# sixties2.net
KiCad netlist of a schematic drawn in EAGLE
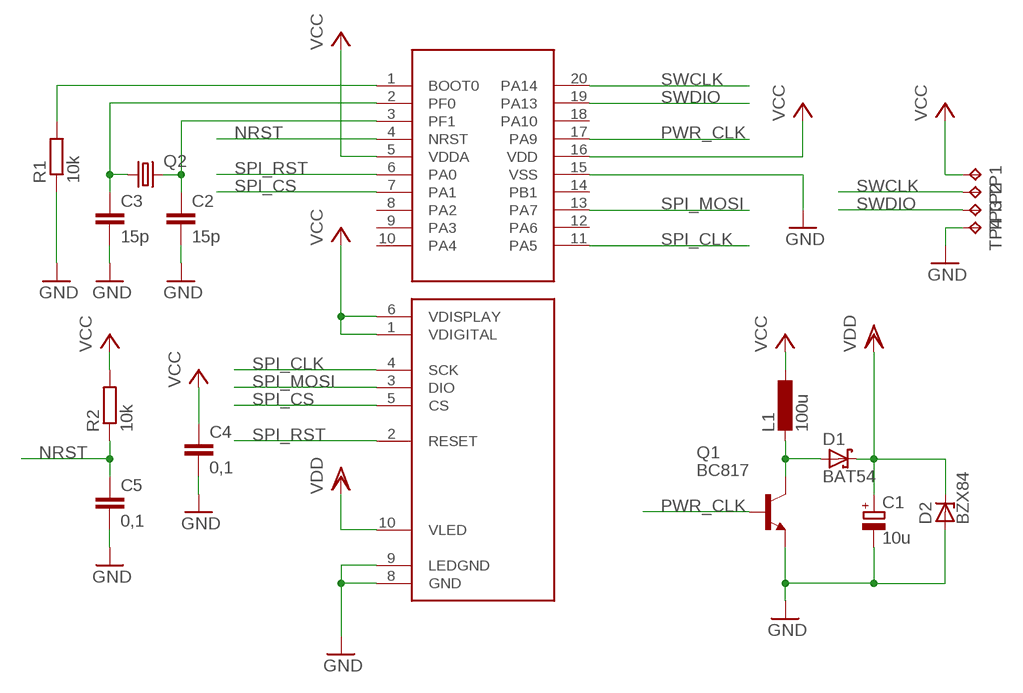
[diagram p0: schematic, sheet 1]

(export (version "E")
  (design (tool "Eeschema 10.0.6"))
  (components
    (comp (ref "C1")
      (value "10u")
      (footprint "eagle-import:D_7343-31W")
      (libsource (lib "eagle-import") (part "CPOL-EUD/7343-31W"))
    )
    (comp (ref "C2")
      (value "15p")
      (footprint "eagle-import:C0805K")
      (libsource (lib "eagle-import") (part "C-EUC0805K"))
    )
    (comp (ref "C3")
      (value "15p")
      (footprint "eagle-import:C0805K")
      (libsource (lib "eagle-import") (part "C-EUC0805K"))
    )
    (comp (ref "C4")
      (value "0,1")
      (footprint "eagle-import:C0805K")
      (libsource (lib "eagle-import") (part "C-EUC0805K"))
    )
    (comp (ref "C5")
      (value "0,1")
      (footprint "eagle-import:C0805K")
      (libsource (lib "eagle-import") (part "C-EUC0805K"))
    )
    (comp (ref "D1")
      (value "BAT54")
      (footprint "eagle-import:SOT23")
      (libsource (lib "eagle-import") (part "BAT54"))
    )
    (comp (ref "D2")
      (value "BZX84")
      (footprint "eagle-import:TO236")
      (libsource (lib "eagle-import") (part "BZX84CSMD"))
    )
    (comp (ref "L1")
      (value "100u")
      (footprint "eagle-import:L1812")
      (libsource (lib "eagle-import") (part "L-EUL1812"))
    )
    (comp (ref "Q1")
      (value "BC817")
      (footprint "eagle-import:SOT23-BEC")
      (libsource (lib "eagle-import") (part "BC817SMD-40"))
    )
    (comp (ref "Q2")
      (value "CRYSTALSM49")
      (footprint "eagle-import:SM49")
      (libsource (lib "eagle-import") (part "CRYSTALSM49"))
    )
    (comp (ref "R1")
      (value "10k")
      (footprint "eagle-import:M0805")
      (libsource (lib "eagle-import") (part "R-EU_M0805"))
    )
    (comp (ref "R2")
      (value "10k")
      (footprint "eagle-import:M0805")
      (libsource (lib "eagle-import") (part "R-EU_M0805"))
    )
    (comp (ref "TP1")
      (value "TPTP11R")
      (footprint "eagle-import:TP11R")
      (libsource (lib "eagle-import") (part "TPTP11R"))
    )
    (comp (ref "TP2")
      (value "TPTP11R")
      (footprint "eagle-import:TP11R")
      (libsource (lib "eagle-import") (part "TPTP11R"))
    )
    (comp (ref "TP3")
      (value "TPTP11R")
      (footprint "eagle-import:TP11R")
      (libsource (lib "eagle-import") (part "TPTP11R"))
    )
    (comp (ref "TP4")
      (value "TPTP11R")
      (footprint "eagle-import:TP11R")
      (libsource (lib "eagle-import") (part "TPTP11R"))
    )
    (comp (ref "U$2")
      (value "NOKIA6100_LCD")
      (footprint "eagle-import:NOKIA6100_LCD")
      (libsource (lib "eagle-import") (part "NOKIA6100_LCD"))
    )
    (comp (ref "U1")
      (value "STM32F030F4")
      (footprint "eagle-import:TSSOP20")
      (libsource (lib "eagle-import") (part "STM32F030F4"))
    )
  )
  (nets
    (net (code "1") (name "/NRST") (class "Default")
      (node (ref "C5") (pin "1") (pinfunction "1_1") (pintype "passive"))
      (node (ref "R2") (pin "1") (pinfunction "1_1") (pintype "passive"))
      (node (ref "U1") (pin "4") (pinfunction "NRST_4") (pintype "bidirectional"))
    )
    (net (code "2") (name "/PWR_CLK") (class "Default")
      (node (ref "Q1") (pin "B") (pinfunction "B_B") (pintype "passive"))
      (node (ref "U1") (pin "17") (pinfunction "PA9_17") (pintype "bidirectional"))
    )
    (net (code "3") (name "/SPI_CLK") (class "Default")
      (node (ref "U$2") (pin "4") (pinfunction "SCK_4") (pintype "bidirectional"))
      (node (ref "U1") (pin "11") (pinfunction "PA5_11") (pintype "bidirectional"))
    )
    (net (code "4") (name "/SPI_CS") (class "Default")
      (node (ref "U$2") (pin "5") (pinfunction "CS_5") (pintype "bidirectional"))
      (node (ref "U1") (pin "7") (pinfunction "PA1_7") (pintype "bidirectional"))
    )
    (net (code "5") (name "/SPI_MOSI") (class "Default")
      (node (ref "U$2") (pin "3") (pinfunction "DIO_3") (pintype "bidirectional"))
      (node (ref "U1") (pin "13") (pinfunction "PA7_13") (pintype "bidirectional"))
    )
    (net (code "6") (name "/SPI_RST") (class "Default")
      (node (ref "U$2") (pin "2") (pinfunction "RESET_2") (pintype "bidirectional"))
      (node (ref "U1") (pin "6") (pinfunction "PA0_6") (pintype "bidirectional"))
    )
    (net (code "7") (name "/SWCLK") (class "Default")
      (node (ref "TP2") (pin "TP") (pinfunction "TP_TP") (pintype "input"))
      (node (ref "U1") (pin "20") (pinfunction "PA14_20") (pintype "bidirectional"))
    )
    (net (code "8") (name "/SWDIO") (class "Default")
      (node (ref "TP3") (pin "TP") (pinfunction "TP_TP") (pintype "input"))
      (node (ref "U1") (pin "19") (pinfunction "PA13_19") (pintype "bidirectional"))
    )
    (net (code "9") (name "GND") (class "Default")
      (node (ref "C1") (pin "-") (pinfunction "-_-") (pintype "passive"))
      (node (ref "C2") (pin "2") (pinfunction "2_2") (pintype "passive"))
      (node (ref "C3") (pin "2") (pinfunction "2_2") (pintype "passive"))
      (node (ref "C4") (pin "2") (pinfunction "2_2") (pintype "passive"))
      (node (ref "C5") (pin "2") (pinfunction "2_2") (pintype "passive"))
      (node (ref "D2") (pin "A") (pinfunction "A_A") (pintype "passive"))
      (node (ref "Q1") (pin "E") (pinfunction "E_E") (pintype "passive"))
      (node (ref "R1") (pin "1") (pinfunction "1_1") (pintype "passive"))
      (node (ref "TP4") (pin "TP") (pinfunction "TP_TP") (pintype "input"))
      (node (ref "U$2") (pin "8") (pinfunction "GND_8") (pintype "bidirectional"))
      (node (ref "U$2") (pin "9") (pinfunction "LEDGND_9") (pintype "bidirectional"))
      (node (ref "U1") (pin "15") (pinfunction "VSS_15") (pintype "bidirectional"))
    )
    (net (code "10") (name "Net-(D1-A)") (class "Default")
      (node (ref "D1") (pin "1") (pinfunction "A_1") (pintype "passive"))
      (node (ref "L1") (pin "2") (pinfunction "2_2") (pintype "passive"))
      (node (ref "Q1") (pin "C") (pinfunction "C_C") (pintype "passive"))
    )
    (net (code "11") (name "Net-(U1-BOOT0)") (class "Default")
      (node (ref "R1") (pin "2") (pinfunction "2_2") (pintype "passive"))
      (node (ref "U1") (pin "1") (pinfunction "BOOT0_1") (pintype "bidirectional"))
    )
    (net (code "12") (name "Net-(U1-PF0)") (class "Default")
      (node (ref "C3") (pin "1") (pinfunction "1_1") (pintype "passive"))
      (node (ref "Q2") (pin "1") (pinfunction "1_1") (pintype "passive"))
      (node (ref "U1") (pin "2") (pinfunction "PF0_2") (pintype "bidirectional"))
    )
    (net (code "13") (name "Net-(U1-PF1)") (class "Default")
      (node (ref "C2") (pin "1") (pinfunction "1_1") (pintype "passive"))
      (node (ref "Q2") (pin "2") (pinfunction "2_2") (pintype "passive"))
      (node (ref "U1") (pin "3") (pinfunction "PF1_3") (pintype "bidirectional"))
    )
    (net (code "14") (name "VCC") (class "Default")
      (node (ref "C4") (pin "1") (pinfunction "1_1") (pintype "passive"))
      (node (ref "L1") (pin "1") (pinfunction "1_1") (pintype "passive"))
      (node (ref "R2") (pin "2") (pinfunction "2_2") (pintype "passive"))
      (node (ref "TP1") (pin "TP") (pinfunction "TP_TP") (pintype "input"))
      (node (ref "U$2") (pin "1") (pinfunction "VDIGITAL_1") (pintype "bidirectional"))
      (node (ref "U$2") (pin "6") (pinfunction "VDISPLAY_6") (pintype "bidirectional"))
      (node (ref "U1") (pin "16") (pinfunction "VDD_16") (pintype "bidirectional"))
      (node (ref "U1") (pin "5") (pinfunction "VDDA_5") (pintype "bidirectional"))
    )
    (net (code "15") (name "VDD") (class "Default")
      (node (ref "C1") (pin "+") (pinfunction "+_+") (pintype "passive"))
      (node (ref "D1") (pin "3") (pinfunction "C_3") (pintype "passive"))
      (node (ref "D2") (pin "C") (pinfunction "C_C") (pintype "passive"))
      (node (ref "U$2") (pin "10") (pinfunction "VLED_10") (pintype "bidirectional"))
    )
    (net (code "16") (name "unconnected-(U1-PA2-Pad8)") (class "Default")
      (node (ref "U1") (pin "8") (pinfunction "PA2_8") (pintype "bidirectional"))
    )
    (net (code "17") (name "unconnected-(U1-PA3-Pad9)") (class "Default")
      (node (ref "U1") (pin "9") (pinfunction "PA3_9") (pintype "bidirectional"))
    )
    (net (code "18") (name "unconnected-(U1-PA4-Pad10)") (class "Default")
      (node (ref "U1") (pin "10") (pinfunction "PA4_10") (pintype "bidirectional"))
    )
    (net (code "19") (name "unconnected-(U1-PA6-Pad12)") (class "Default")
      (node (ref "U1") (pin "12") (pinfunction "PA6_12") (pintype "bidirectional"))
    )
    (net (code "20") (name "unconnected-(U1-PA10-Pad18)") (class "Default")
      (node (ref "U1") (pin "18") (pinfunction "PA10_18") (pintype "bidirectional"))
    )
    (net (code "21") (name "unconnected-(U1-PB1-Pad14)") (class "Default")
      (node (ref "U1") (pin "14") (pinfunction "PB1_14") (pintype "bidirectional"))
    )
  )
)
